# VoltageControlledEuclideanSequencer.net
KiCad netlist of a schematic drawn in EAGLE
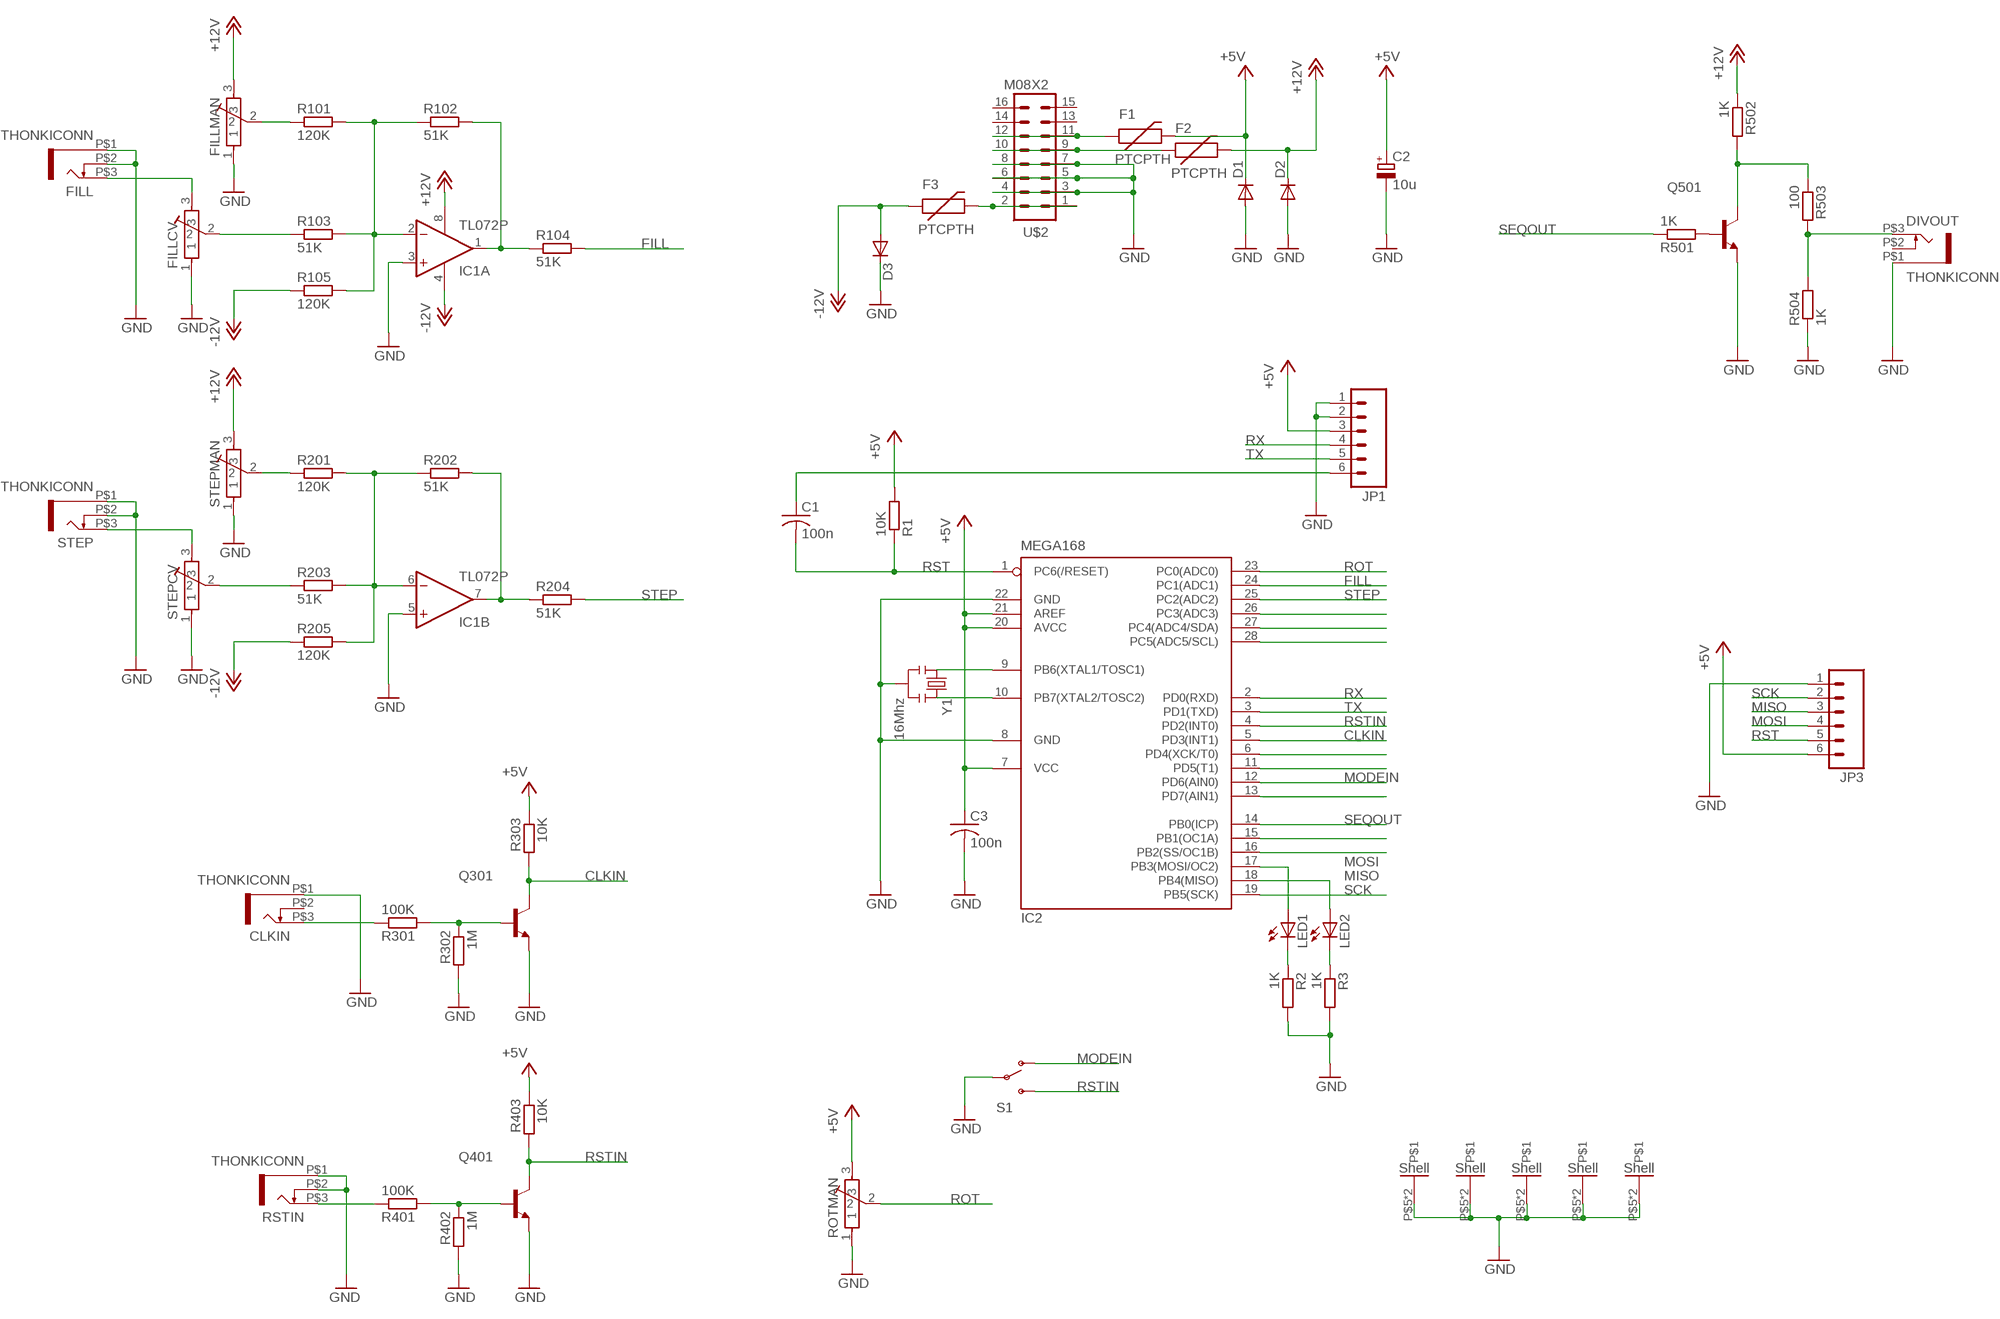
[diagram p0: schematic, sheet 1]

(export (version "E")
  (design (tool "Eeschema 10.0.6"))
  (components
    (comp (ref "C1")
      (value "100n")
      (footprint "eagle-import:C050-024X044")
      (libsource (lib "eagle-import") (part "C-US050-024X044"))
    )
    (comp (ref "C2")
      (value "10u")
      (footprint "eagle-import:E2,5-6")
      (libsource (lib "eagle-import") (part "CPOL-EUE2.5-6"))
    )
    (comp (ref "C3")
      (value "100n")
      (footprint "eagle-import:C050-024X044")
      (libsource (lib "eagle-import") (part "C-US050-024X044"))
    )
    (comp (ref "CLKIN")
      (value "THONKICONN")
      (footprint "eagle-import:THONKICONN")
      (libsource (lib "eagle-import") (part "THONKICONN"))
    )
    (comp (ref "D1")
      (value "DIODE1N4001")
      (footprint "eagle-import:DIODE-1N4001")
      (libsource (lib "eagle-import") (part "DIODE1N4001"))
    )
    (comp (ref "D2")
      (value "DIODE1N4001")
      (footprint "eagle-import:DIODE-1N4001")
      (libsource (lib "eagle-import") (part "DIODE1N4001"))
    )
    (comp (ref "D3")
      (value "DIODE1N4001")
      (footprint "eagle-import:DIODE-1N4001")
      (libsource (lib "eagle-import") (part "DIODE1N4001"))
    )
    (comp (ref "DIVOUT")
      (value "THONKICONN")
      (footprint "eagle-import:THONKICONN")
      (libsource (lib "eagle-import") (part "THONKICONN"))
    )
    (comp (ref "F1")
      (value "PTCPTH")
      (footprint "eagle-import:PTC")
      (libsource (lib "eagle-import") (part "PTCPTH"))
    )
    (comp (ref "F2")
      (value "PTCPTH")
      (footprint "eagle-import:PTC")
      (libsource (lib "eagle-import") (part "PTCPTH"))
    )
    (comp (ref "F3")
      (value "PTCPTH")
      (footprint "eagle-import:PTC")
      (libsource (lib "eagle-import") (part "PTCPTH"))
    )
    (comp (ref "FILL")
      (value "THONKICONN")
      (footprint "eagle-import:THONKICONN")
      (libsource (lib "eagle-import") (part "THONKICONN"))
    )
    (comp (ref "FILLCV")
      (value "POT-ALPS-RK09L1140")
      (footprint "eagle-import:POT-ALPS-RK09L1140")
      (libsource (lib "eagle-import") (part "POT-ALPS-RK09L1140"))
    )
    (comp (ref "FILLMAN")
      (value "POT-ALPS-RK09L1140")
      (footprint "eagle-import:POT-ALPS-RK09L1140")
      (libsource (lib "eagle-import") (part "POT-ALPS-RK09L1140"))
    )
    (comp (ref "IC1")
      (value "TL072P")
      (footprint "eagle-import:DIL08")
      (libsource (lib "eagle-import") (part "TL072P"))
    )
    (comp (ref "IC2")
      (value "MEGA168")
      (footprint "eagle-import:DIL28-3")
      (libsource (lib "eagle-import") (part "MEGA8-P"))
    )
    (comp (ref "JP1")
      (value "M06SIP")
      (footprint "eagle-import:1X06")
      (libsource (lib "eagle-import") (part "M06SIP"))
    )
    (comp (ref "JP3")
      (value "M06SIP")
      (footprint "eagle-import:1X06")
      (libsource (lib "eagle-import") (part "M06SIP"))
    )
    (comp (ref "LED1")
      (value "LED3MM")
      (footprint "eagle-import:LED3MM")
      (libsource (lib "eagle-import") (part "LED3MM"))
    )
    (comp (ref "LED2")
      (value "LED3MM")
      (footprint "eagle-import:LED3MM")
      (libsource (lib "eagle-import") (part "LED3MM"))
    )
    (comp (ref "Q301")
      (value "2N3904-NPN-TO92-EBC")
      (footprint "eagle-import:TO92-EBC")
      (libsource (lib "eagle-import") (part "-NPN-TO92-EBC2N3904"))
    )
    (comp (ref "Q401")
      (value "2N3904-NPN-TO92-EBC")
      (footprint "eagle-import:TO92-EBC")
      (libsource (lib "eagle-import") (part "-NPN-TO92-EBC2N3904"))
    )
    (comp (ref "Q501")
      (value "2N3904-NPN-TO92-EBC")
      (footprint "eagle-import:TO92-EBC")
      (libsource (lib "eagle-import") (part "-NPN-TO92-EBC2N3904"))
    )
    (comp (ref "R1")
      (value "10K")
      (footprint "eagle-import:0204_7")
      (libsource (lib "eagle-import") (part "R-EU_0204/7"))
    )
    (comp (ref "R2")
      (value "1K")
      (footprint "eagle-import:0204_7")
      (libsource (lib "eagle-import") (part "R-EU_0204/7"))
    )
    (comp (ref "R3")
      (value "1K")
      (footprint "eagle-import:0204_7")
      (libsource (lib "eagle-import") (part "R-EU_0204/7"))
    )
    (comp (ref "R101")
      (value "120K")
      (footprint "eagle-import:0204_7")
      (libsource (lib "eagle-import") (part "R-EU_0204/7"))
    )
    (comp (ref "R102")
      (value "51K")
      (footprint "eagle-import:0204_7")
      (libsource (lib "eagle-import") (part "R-EU_0204/7"))
    )
    (comp (ref "R103")
      (value "51K")
      (footprint "eagle-import:0204_7")
      (libsource (lib "eagle-import") (part "R-EU_0204/7"))
    )
    (comp (ref "R104")
      (value "51K")
      (footprint "eagle-import:0204_7")
      (libsource (lib "eagle-import") (part "R-EU_0204/7"))
    )
    (comp (ref "R105")
      (value "120K")
      (footprint "eagle-import:0204_7")
      (libsource (lib "eagle-import") (part "R-EU_0204/7"))
    )
    (comp (ref "R201")
      (value "120K")
      (footprint "eagle-import:0204_7")
      (libsource (lib "eagle-import") (part "R-EU_0204/7"))
    )
    (comp (ref "R202")
      (value "51K")
      (footprint "eagle-import:0204_7")
      (libsource (lib "eagle-import") (part "R-EU_0204/7"))
    )
    (comp (ref "R203")
      (value "51K")
      (footprint "eagle-import:0204_7")
      (libsource (lib "eagle-import") (part "R-EU_0204/7"))
    )
    (comp (ref "R204")
      (value "51K")
      (footprint "eagle-import:0204_7")
      (libsource (lib "eagle-import") (part "R-EU_0204/7"))
    )
    (comp (ref "R205")
      (value "120K")
      (footprint "eagle-import:0204_7")
      (libsource (lib "eagle-import") (part "R-EU_0204/7"))
    )
    (comp (ref "R301")
      (value "100K")
      (footprint "eagle-import:0204_7")
      (libsource (lib "eagle-import") (part "R-EU_0204/7"))
    )
    (comp (ref "R302")
      (value "1M")
      (footprint "eagle-import:0204_7")
      (libsource (lib "eagle-import") (part "R-EU_0204/7"))
    )
    (comp (ref "R303")
      (value "10K")
      (footprint "eagle-import:0204_7")
      (libsource (lib "eagle-import") (part "R-EU_0204/7"))
    )
    (comp (ref "R401")
      (value "100K")
      (footprint "eagle-import:0204_7")
      (libsource (lib "eagle-import") (part "R-EU_0204/7"))
    )
    (comp (ref "R402")
      (value "1M")
      (footprint "eagle-import:0204_7")
      (libsource (lib "eagle-import") (part "R-EU_0204/7"))
    )
    (comp (ref "R403")
      (value "10K")
      (footprint "eagle-import:0204_7")
      (libsource (lib "eagle-import") (part "R-EU_0204/7"))
    )
    (comp (ref "R501")
      (value "1K")
      (footprint "eagle-import:0204_7")
      (libsource (lib "eagle-import") (part "R-EU_0204/7"))
    )
    (comp (ref "R502")
      (value "1K")
      (footprint "eagle-import:0204_7")
      (libsource (lib "eagle-import") (part "R-EU_0204/7"))
    )
    (comp (ref "R503")
      (value "100")
      (footprint "eagle-import:0204_7")
      (libsource (lib "eagle-import") (part "R-EU_0204/7"))
    )
    (comp (ref "R504")
      (value "1K")
      (footprint "eagle-import:0204_7")
      (libsource (lib "eagle-import") (part "R-EU_0204/7"))
    )
    (comp (ref "ROTMAN")
      (value "POT-ALPS-RK09L1140")
      (footprint "eagle-import:POT-ALPS-RK09L1140")
      (libsource (lib "eagle-import") (part "POT-ALPS-RK09L1140"))
    )
    (comp (ref "RSTIN")
      (value "THONKICONN")
      (footprint "eagle-import:THONKICONN")
      (libsource (lib "eagle-import") (part "THONKICONN"))
    )
    (comp (ref "S1")
      (value "SWITCH-SPST")
      (footprint "eagle-import:SWITCH-SPDT-SALECOM-T8014")
      (libsource (lib "eagle-import") (part "SWITCH-SPST"))
    )
    (comp (ref "STEP")
      (value "THONKICONN")
      (footprint "eagle-import:THONKICONN")
      (libsource (lib "eagle-import") (part "THONKICONN"))
    )
    (comp (ref "STEPCV")
      (value "POT-ALPS-RK09L1140")
      (footprint "eagle-import:POT-ALPS-RK09L1140")
      (libsource (lib "eagle-import") (part "POT-ALPS-RK09L1140"))
    )
    (comp (ref "STEPMAN")
      (value "POT-ALPS-RK09L1140")
      (footprint "eagle-import:POT-ALPS-RK09L1140")
      (libsource (lib "eagle-import") (part "POT-ALPS-RK09L1140"))
    )
    (comp (ref "U$2")
      (value "M08X2")
      (footprint "eagle-import:2X8")
      (libsource (lib "eagle-import") (part "M08X2"))
    )
    (comp (ref "Y1")
      (value "16Mhz")
      (footprint "eagle-import:RESONATOR-PTH")
      (libsource (lib "eagle-import") (part "RESONATORPTH"))
    )
  )
  (nets
    (net (code "1") (name "+5V") (class "Default")
      (node (ref "C2") (pin "+") (pinfunction "+_+") (pintype "passive"))
      (node (ref "C3") (pin "1") (pinfunction "1_1") (pintype "passive"))
      (node (ref "D1") (pin "C") (pinfunction "C_C") (pintype "passive"))
      (node (ref "F1") (pin "P$2") (pinfunction "2_P$2") (pintype "bidirectional"))
      (node (ref "IC2") (pin "20") (pinfunction "AVCC_20") (pintype "power_in"))
      (node (ref "IC2") (pin "21") (pinfunction "AREF_21") (pintype "passive"))
      (node (ref "IC2") (pin "7") (pinfunction "VCC_7") (pintype "power_in"))
      (node (ref "JP1") (pin "3") (pinfunction "3_3") (pintype "passive"))
      (node (ref "JP3") (pin "6") (pinfunction "6_6") (pintype "passive"))
      (node (ref "R1") (pin "2") (pinfunction "2_2") (pintype "passive"))
      (node (ref "R303") (pin "1") (pinfunction "1_1") (pintype "passive"))
      (node (ref "R403") (pin "1") (pinfunction "1_1") (pintype "passive"))
      (node (ref "ROTMAN") (pin "3") (pinfunction "3_3") (pintype "bidirectional"))
    )
    (net (code "2") (name "+12V") (class "Default")
      (node (ref "D2") (pin "C") (pinfunction "C_C") (pintype "passive"))
      (node (ref "F2") (pin "P$2") (pinfunction "2_P$2") (pintype "bidirectional"))
      (node (ref "FILLMAN") (pin "3") (pinfunction "3_3") (pintype "bidirectional"))
      (node (ref "IC1") (pin "8") (pinfunction "V+_8") (pintype "power_in"))
      (node (ref "R502") (pin "1") (pinfunction "1_1") (pintype "passive"))
      (node (ref "STEPMAN") (pin "3") (pinfunction "3_3") (pintype "bidirectional"))
    )
    (net (code "3") (name "-12V") (class "Default")
      (node (ref "D3") (pin "A") (pinfunction "A_A") (pintype "passive"))
      (node (ref "F3") (pin "P$1") (pinfunction "1_P$1") (pintype "bidirectional"))
      (node (ref "IC1") (pin "4") (pinfunction "V-_4") (pintype "power_in"))
      (node (ref "R105") (pin "1") (pinfunction "1_1") (pintype "passive"))
      (node (ref "R205") (pin "1") (pinfunction "1_1") (pintype "passive"))
    )
    (net (code "4") (name "/CLKIN") (class "Default")
      (node (ref "IC2") (pin "5") (pinfunction "PD3(INT1)_5") (pintype "bidirectional"))
      (node (ref "Q301") (pin "C") (pinfunction "C_C") (pintype "passive"))
      (node (ref "R303") (pin "2") (pinfunction "2_2") (pintype "passive"))
    )
    (net (code "5") (name "/FILL") (class "Default")
      (node (ref "IC2") (pin "24") (pinfunction "PC1(ADC1)_24") (pintype "bidirectional"))
      (node (ref "R104") (pin "2") (pinfunction "2_2") (pintype "passive"))
    )
    (net (code "6") (name "/MISO") (class "Default")
      (node (ref "IC2") (pin "18") (pinfunction "PB4(MISO)_18") (pintype "bidirectional"))
      (node (ref "JP3") (pin "3") (pinfunction "3_3") (pintype "passive"))
      (node (ref "LED2") (pin "A") (pinfunction "A_A") (pintype "passive"))
    )
    (net (code "7") (name "/MODEIN") (class "Default")
      (node (ref "IC2") (pin "12") (pinfunction "PD6(AIN0)_12") (pintype "bidirectional"))
      (node (ref "S1") (pin "1") (pinfunction "O_1") (pintype "passive"))
    )
    (net (code "8") (name "/MOSI") (class "Default")
      (node (ref "IC2") (pin "17") (pinfunction "PB3(MOSI/OC2)_17") (pintype "bidirectional"))
      (node (ref "JP3") (pin "4") (pinfunction "4_4") (pintype "passive"))
      (node (ref "LED1") (pin "A") (pinfunction "A_A") (pintype "passive"))
    )
    (net (code "9") (name "/ROT") (class "Default")
      (node (ref "IC2") (pin "23") (pinfunction "PC0(ADC0)_23") (pintype "bidirectional"))
      (node (ref "ROTMAN") (pin "2") (pinfunction "2_2") (pintype "bidirectional"))
    )
    (net (code "10") (name "/RST") (class "Default")
      (node (ref "C1") (pin "2") (pinfunction "2_2") (pintype "passive"))
      (node (ref "IC2") (pin "1") (pinfunction "PC6(/RESET)_1") (pintype "bidirectional"))
      (node (ref "JP3") (pin "5") (pinfunction "5_5") (pintype "passive"))
      (node (ref "R1") (pin "1") (pinfunction "1_1") (pintype "passive"))
    )
    (net (code "11") (name "/RSTIN") (class "Default")
      (node (ref "IC2") (pin "4") (pinfunction "PD2(INT0)_4") (pintype "bidirectional"))
      (node (ref "Q401") (pin "C") (pinfunction "C_C") (pintype "passive"))
      (node (ref "R403") (pin "2") (pinfunction "2_2") (pintype "passive"))
      (node (ref "S1") (pin "3") (pinfunction "S_3") (pintype "passive"))
    )
    (net (code "12") (name "/RX") (class "Default")
      (node (ref "IC2") (pin "2") (pinfunction "PD0(RXD)_2") (pintype "bidirectional"))
      (node (ref "JP1") (pin "4") (pinfunction "4_4") (pintype "passive"))
    )
    (net (code "13") (name "/SCK") (class "Default")
      (node (ref "IC2") (pin "19") (pinfunction "PB5(SCK)_19") (pintype "bidirectional"))
      (node (ref "JP3") (pin "2") (pinfunction "2_2") (pintype "passive"))
    )
    (net (code "14") (name "/SEQOUT") (class "Default")
      (node (ref "IC2") (pin "14") (pinfunction "PB0(ICP)_14") (pintype "bidirectional"))
      (node (ref "R501") (pin "1") (pinfunction "1_1") (pintype "passive"))
    )
    (net (code "15") (name "/STEP") (class "Default")
      (node (ref "IC2") (pin "25") (pinfunction "PC2(ADC2)_25") (pintype "bidirectional"))
      (node (ref "R204") (pin "2") (pinfunction "2_2") (pintype "passive"))
    )
    (net (code "16") (name "/TX") (class "Default")
      (node (ref "IC2") (pin "3") (pinfunction "PD1(TXD)_3") (pintype "bidirectional"))
      (node (ref "JP1") (pin "5") (pinfunction "5_5") (pintype "passive"))
    )
    (net (code "17") (name "GND") (class "Default")
      (node (ref "C2") (pin "-") (pinfunction "-_-") (pintype "passive"))
      (node (ref "C3") (pin "2") (pinfunction "2_2") (pintype "passive"))
      (node (ref "CLKIN") (pin "P$1") (pinfunction "5_P$1") (pintype "passive"))
      (node (ref "D1") (pin "A") (pinfunction "A_A") (pintype "passive"))
      (node (ref "D2") (pin "A") (pinfunction "A_A") (pintype "passive"))
      (node (ref "D3") (pin "C") (pinfunction "C_C") (pintype "passive"))
      (node (ref "DIVOUT") (pin "P$1") (pinfunction "5_P$1") (pintype "passive"))
      (node (ref "FILL") (pin "P$1") (pinfunction "5_P$1") (pintype "passive"))
      (node (ref "FILL") (pin "P$2") (pinfunction "4_P$2") (pintype "passive"))
      (node (ref "FILLCV") (pin "1") (pinfunction "1_1") (pintype "bidirectional"))
      (node (ref "FILLCV") (pin "P$5") (pinfunction "P$1_P$5") (pintype "bidirectional"))
      (node (ref "FILLCV") (pin "P$6") (pinfunction "P$1_P$6") (pintype "bidirectional"))
      (node (ref "FILLMAN") (pin "1") (pinfunction "1_1") (pintype "bidirectional"))
      (node (ref "FILLMAN") (pin "P$5") (pinfunction "P$1_P$5") (pintype "bidirectional"))
      (node (ref "FILLMAN") (pin "P$6") (pinfunction "P$1_P$6") (pintype "bidirectional"))
      (node (ref "IC1") (pin "3") (pinfunction "+IN_3") (pintype "input"))
      (node (ref "IC1") (pin "5") (pinfunction "+IN_5") (pintype "input"))
      (node (ref "IC2") (pin "22") (pinfunction "GND_22") (pintype "power_in"))
      (node (ref "IC2") (pin "8") (pinfunction "GND_8") (pintype "power_in"))
      (node (ref "JP1") (pin "1") (pinfunction "1_1") (pintype "passive"))
      (node (ref "JP1") (pin "2") (pinfunction "2_2") (pintype "passive"))
      (node (ref "JP3") (pin "1") (pinfunction "1_1") (pintype "passive"))
      (node (ref "Q301") (pin "E") (pinfunction "E_E") (pintype "passive"))
      (node (ref "Q401") (pin "E") (pinfunction "E_E") (pintype "passive"))
      (node (ref "Q501") (pin "E") (pinfunction "E_E") (pintype "passive"))
      (node (ref "R2") (pin "2") (pinfunction "2_2") (pintype "passive"))
      (node (ref "R3") (pin "2") (pinfunction "2_2") (pintype "passive"))
      (node (ref "R302") (pin "2") (pinfunction "2_2") (pintype "passive"))
      (node (ref "R402") (pin "2") (pinfunction "2_2") (pintype "passive"))
      (node (ref "R504") (pin "1") (pinfunction "1_1") (pintype "passive"))
      (node (ref "ROTMAN") (pin "1") (pinfunction "1_1") (pintype "bidirectional"))
      (node (ref "ROTMAN") (pin "P$5") (pinfunction "P$1_P$5") (pintype "bidirectional"))
      (node (ref "ROTMAN") (pin "P$6") (pinfunction "P$1_P$6") (pintype "bidirectional"))
      (node (ref "RSTIN") (pin "P$1") (pinfunction "5_P$1") (pintype "passive"))
      (node (ref "RSTIN") (pin "P$2") (pinfunction "4_P$2") (pintype "passive"))
      (node (ref "S1") (pin "2") (pinfunction "P_2") (pintype "passive"))
      (node (ref "STEP") (pin "P$1") (pinfunction "5_P$1") (pintype "passive"))
      (node (ref "STEP") (pin "P$2") (pinfunction "4_P$2") (pintype "passive"))
      (node (ref "STEPCV") (pin "1") (pinfunction "1_1") (pintype "bidirectional"))
      (node (ref "STEPCV") (pin "P$5") (pinfunction "P$1_P$5") (pintype "bidirectional"))
      (node (ref "STEPCV") (pin "P$6") (pinfunction "P$1_P$6") (pintype "bidirectional"))
      (node (ref "STEPMAN") (pin "1") (pinfunction "1_1") (pintype "bidirectional"))
      (node (ref "STEPMAN") (pin "P$5") (pinfunction "P$1_P$5") (pintype "bidirectional"))
      (node (ref "STEPMAN") (pin "P$6") (pinfunction "P$1_P$6") (pintype "bidirectional"))
      (node (ref "U$2") (pin "3") (pinfunction "3_3") (pintype "passive"))
      (node (ref "U$2") (pin "4") (pinfunction "4_4") (pintype "passive"))
      (node (ref "U$2") (pin "5") (pinfunction "5_5") (pintype "passive"))
      (node (ref "U$2") (pin "6") (pinfunction "6_6") (pintype "passive"))
      (node (ref "U$2") (pin "7") (pinfunction "7_7") (pintype "passive"))
      (node (ref "U$2") (pin "8") (pinfunction "8_8") (pintype "passive"))
      (node (ref "Y1") (pin "2") (pinfunction "2_2") (pintype "passive"))
    )
    (net (code "18") (name "Net-(C1-Pad1)") (class "Default")
      (node (ref "C1") (pin "1") (pinfunction "1_1") (pintype "passive"))
      (node (ref "JP1") (pin "6") (pinfunction "6_6") (pintype "passive"))
    )
    (net (code "19") (name "Net-(CLKIN-3)") (class "Default")
      (node (ref "CLKIN") (pin "P$3") (pinfunction "3_P$3") (pintype "passive"))
      (node (ref "R301") (pin "1") (pinfunction "1_1") (pintype "passive"))
    )
    (net (code "20") (name "Net-(DIVOUT-3)") (class "Default")
      (node (ref "DIVOUT") (pin "P$3") (pinfunction "3_P$3") (pintype "passive"))
      (node (ref "R503") (pin "2") (pinfunction "2_2") (pintype "passive"))
      (node (ref "R504") (pin "2") (pinfunction "2_2") (pintype "passive"))
    )
    (net (code "21") (name "Net-(F1-1)") (class "Default")
      (node (ref "F1") (pin "P$1") (pinfunction "1_P$1") (pintype "bidirectional"))
      (node (ref "U$2") (pin "11") (pinfunction "11_11") (pintype "passive"))
      (node (ref "U$2") (pin "12") (pinfunction "12_12") (pintype "passive"))
    )
    (net (code "22") (name "Net-(F2-1)") (class "Default")
      (node (ref "F2") (pin "P$1") (pinfunction "1_P$1") (pintype "bidirectional"))
      (node (ref "U$2") (pin "10") (pinfunction "10_10") (pintype "passive"))
      (node (ref "U$2") (pin "9") (pinfunction "9_9") (pintype "passive"))
    )
    (net (code "23") (name "Net-(F3-2)") (class "Default")
      (node (ref "F3") (pin "P$2") (pinfunction "2_P$2") (pintype "bidirectional"))
      (node (ref "U$2") (pin "1") (pinfunction "1_1") (pintype "passive"))
      (node (ref "U$2") (pin "2") (pinfunction "2_2") (pintype "passive"))
    )
    (net (code "24") (name "Net-(FILL-3)") (class "Default")
      (node (ref "FILL") (pin "P$3") (pinfunction "3_P$3") (pintype "passive"))
      (node (ref "FILLCV") (pin "3") (pinfunction "3_3") (pintype "bidirectional"))
    )
    (net (code "25") (name "Net-(FILLCV-Pad2)") (class "Default")
      (node (ref "FILLCV") (pin "2") (pinfunction "2_2") (pintype "bidirectional"))
      (node (ref "R103") (pin "1") (pinfunction "1_1") (pintype "passive"))
    )
    (net (code "26") (name "Net-(FILLMAN-Pad2)") (class "Default")
      (node (ref "FILLMAN") (pin "2") (pinfunction "2_2") (pintype "bidirectional"))
      (node (ref "R101") (pin "1") (pinfunction "1_1") (pintype "passive"))
    )
    (net (code "27") (name "Net-(IC1A--IN)") (class "Default")
      (node (ref "IC1") (pin "2") (pinfunction "-IN_2") (pintype "input"))
      (node (ref "R101") (pin "2") (pinfunction "2_2") (pintype "passive"))
      (node (ref "R102") (pin "1") (pinfunction "1_1") (pintype "passive"))
      (node (ref "R103") (pin "2") (pinfunction "2_2") (pintype "passive"))
      (node (ref "R105") (pin "2") (pinfunction "2_2") (pintype "passive"))
    )
    (net (code "28") (name "Net-(IC1A-OUT)") (class "Default")
      (node (ref "IC1") (pin "1") (pinfunction "OUT_1") (pintype "output"))
      (node (ref "R102") (pin "2") (pinfunction "2_2") (pintype "passive"))
      (node (ref "R104") (pin "1") (pinfunction "1_1") (pintype "passive"))
    )
    (net (code "29") (name "Net-(IC1B--IN)") (class "Default")
      (node (ref "IC1") (pin "6") (pinfunction "-IN_6") (pintype "input"))
      (node (ref "R201") (pin "2") (pinfunction "2_2") (pintype "passive"))
      (node (ref "R202") (pin "1") (pinfunction "1_1") (pintype "passive"))
      (node (ref "R203") (pin "2") (pinfunction "2_2") (pintype "passive"))
      (node (ref "R205") (pin "2") (pinfunction "2_2") (pintype "passive"))
    )
    (net (code "30") (name "Net-(IC1B-OUT)") (class "Default")
      (node (ref "IC1") (pin "7") (pinfunction "OUT_7") (pintype "output"))
      (node (ref "R202") (pin "2") (pinfunction "2_2") (pintype "passive"))
      (node (ref "R204") (pin "1") (pinfunction "1_1") (pintype "passive"))
    )
    (net (code "31") (name "Net-(IC2-PB6(XTAL1{slash}TOSC1))") (class "Default")
      (node (ref "IC2") (pin "9") (pinfunction "PB6(XTAL1/TOSC1)_9") (pintype "bidirectional"))
      (node (ref "Y1") (pin "1") (pinfunction "1_1") (pintype "passive"))
    )
    (net (code "32") (name "Net-(IC2-PB7(XTAL2{slash}TOSC2))") (class "Default")
      (node (ref "IC2") (pin "10") (pinfunction "PB7(XTAL2/TOSC2)_10") (pintype "bidirectional"))
      (node (ref "Y1") (pin "3") (pinfunction "3_3") (pintype "passive"))
    )
    (net (code "33") (name "Net-(LED1-C)") (class "Default")
      (node (ref "LED1") (pin "K") (pinfunction "C_K") (pintype "passive"))
      (node (ref "R2") (pin "1") (pinfunction "1_1") (pintype "passive"))
    )
    (net (code "34") (name "Net-(LED2-C)") (class "Default")
      (node (ref "LED2") (pin "K") (pinfunction "C_K") (pintype "passive"))
      (node (ref "R3") (pin "1") (pinfunction "1_1") (pintype "passive"))
    )
    (net (code "35") (name "Net-(Q301-PadB)") (class "Default")
      (node (ref "Q301") (pin "B") (pinfunction "B_B") (pintype "passive"))
      (node (ref "R301") (pin "2") (pinfunction "2_2") (pintype "passive"))
      (node (ref "R302") (pin "1") (pinfunction "1_1") (pintype "passive"))
    )
    (net (code "36") (name "Net-(Q401-PadB)") (class "Default")
      (node (ref "Q401") (pin "B") (pinfunction "B_B") (pintype "passive"))
      (node (ref "R401") (pin "2") (pinfunction "2_2") (pintype "passive"))
      (node (ref "R402") (pin "1") (pinfunction "1_1") (pintype "passive"))
    )
    (net (code "37") (name "Net-(Q501-PadB)") (class "Default")
      (node (ref "Q501") (pin "B") (pinfunction "B_B") (pintype "passive"))
      (node (ref "R501") (pin "2") (pinfunction "2_2") (pintype "passive"))
    )
    (net (code "38") (name "Net-(Q501-PadC)") (class "Default")
      (node (ref "Q501") (pin "C") (pinfunction "C_C") (pintype "passive"))
      (node (ref "R502") (pin "2") (pinfunction "2_2") (pintype "passive"))
      (node (ref "R503") (pin "1") (pinfunction "1_1") (pintype "passive"))
    )
    (net (code "39") (name "Net-(R201-Pad1)") (class "Default")
      (node (ref "R201") (pin "1") (pinfunction "1_1") (pintype "passive"))
      (node (ref "STEPMAN") (pin "2") (pinfunction "2_2") (pintype "bidirectional"))
    )
    (net (code "40") (name "Net-(R203-Pad1)") (class "Default")
      (node (ref "R203") (pin "1") (pinfunction "1_1") (pintype "passive"))
      (node (ref "STEPCV") (pin "2") (pinfunction "2_2") (pintype "bidirectional"))
    )
    (net (code "41") (name "Net-(RSTIN-3)") (class "Default")
      (node (ref "R401") (pin "1") (pinfunction "1_1") (pintype "passive"))
      (node (ref "RSTIN") (pin "P$3") (pinfunction "3_P$3") (pintype "passive"))
    )
    (net (code "42") (name "Net-(STEP-3)") (class "Default")
      (node (ref "STEP") (pin "P$3") (pinfunction "3_P$3") (pintype "passive"))
      (node (ref "STEPCV") (pin "3") (pinfunction "3_3") (pintype "bidirectional"))
    )
    (net (code "43") (name "unconnected-(CLKIN-4-PadP$2)") (class "Default")
      (node (ref "CLKIN") (pin "P$2") (pinfunction "4_P$2") (pintype "passive"))
    )
    (net (code "44") (name "unconnected-(DIVOUT-4-PadP$2)") (class "Default")
      (node (ref "DIVOUT") (pin "P$2") (pinfunction "4_P$2") (pintype "passive"))
    )
    (net (code "45") (name "unconnected-(IC2-PB1(OC1A)-Pad15)") (class "Default")
      (node (ref "IC2") (pin "15") (pinfunction "PB1(OC1A)_15") (pintype "bidirectional"))
    )
    (net (code "46") (name "unconnected-(IC2-PB2(SS{slash}OC1B)-Pad16)") (class "Default")
      (node (ref "IC2") (pin "16") (pinfunction "PB2(SS/OC1B)_16") (pintype "bidirectional"))
    )
    (net (code "47") (name "unconnected-(IC2-PC3(ADC3)-Pad26)") (class "Default")
      (node (ref "IC2") (pin "26") (pinfunction "PC3(ADC3)_26") (pintype "bidirectional"))
    )
    (net (code "48") (name "unconnected-(IC2-PC4(ADC4{slash}SDA)-Pad27)") (class "Default")
      (node (ref "IC2") (pin "27") (pinfunction "PC4(ADC4/SDA)_27") (pintype "bidirectional"))
    )
    (net (code "49") (name "unconnected-(IC2-PC5(ADC5{slash}SCL)-Pad28)") (class "Default")
      (node (ref "IC2") (pin "28") (pinfunction "PC5(ADC5/SCL)_28") (pintype "bidirectional"))
    )
    (net (code "50") (name "unconnected-(IC2-PD4(XCK{slash}T0)-Pad6)") (class "Default")
      (node (ref "IC2") (pin "6") (pinfunction "PD4(XCK/T0)_6") (pintype "bidirectional"))
    )
    (net (code "51") (name "unconnected-(IC2-PD5(T1)-Pad11)") (class "Default")
      (node (ref "IC2") (pin "11") (pinfunction "PD5(T1)_11") (pintype "bidirectional"))
    )
    (net (code "52") (name "unconnected-(IC2-PD7(AIN1)-Pad13)") (class "Default")
      (node (ref "IC2") (pin "13") (pinfunction "PD7(AIN1)_13") (pintype "bidirectional"))
    )
    (net (code "53") (name "unconnected-(U$2-Pad13)") (class "Default")
      (node (ref "U$2") (pin "13") (pinfunction "13_13") (pintype "passive"))
    )
    (net (code "54") (name "unconnected-(U$2-Pad14)") (class "Default")
      (node (ref "U$2") (pin "14") (pinfunction "14_14") (pintype "passive"))
    )
    (net (code "55") (name "unconnected-(U$2-Pad15)") (class "Default")
      (node (ref "U$2") (pin "15") (pinfunction "15_15") (pintype "passive"))
    )
    (net (code "56") (name "unconnected-(U$2-Pad16)") (class "Default")
      (node (ref "U$2") (pin "16") (pinfunction "16_16") (pintype "passive"))
    )
  )
)
